# Temctrl_O.net
KiCad netlist of a schematic drawn in Altium Designer
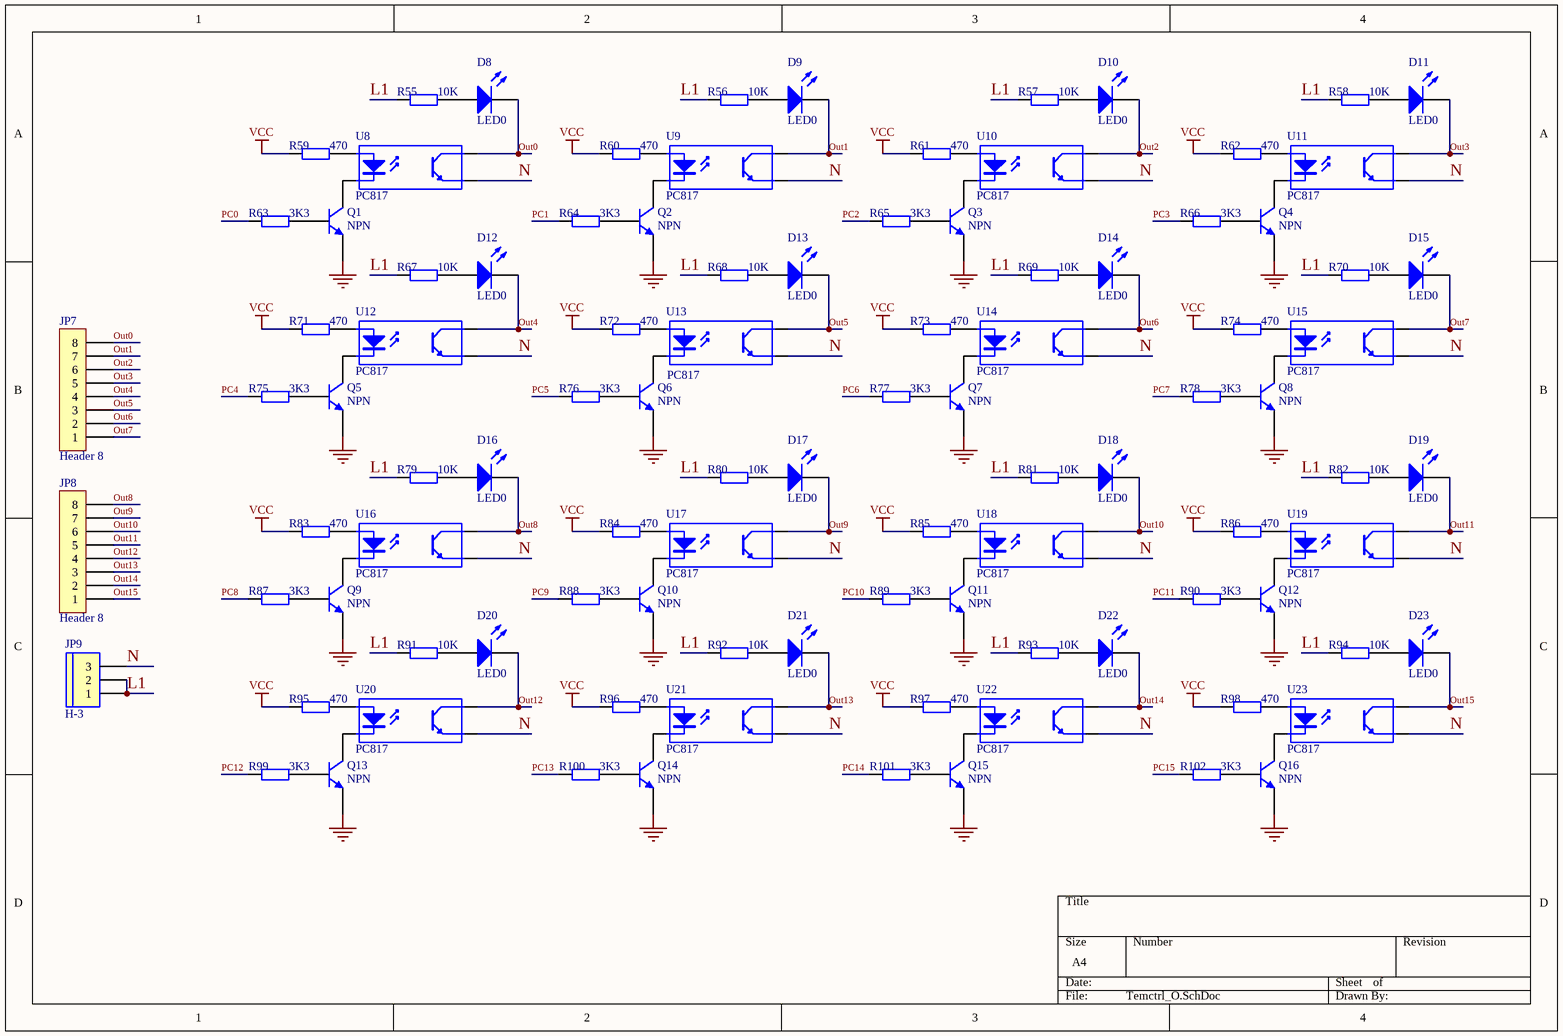
[diagram p0: Temctrl_O.SchDoc]

(export (version "E")
  (design (tool "Eeschema 10.0.6"))
  (components
    (comp (ref "D8")
      (value "LED0")
      (footprint "LED0.1-0.22")
      (description "Typical INFRARED GaAs LED")
      (fields (field (name "PUBLISHER") "Altium Limited"))
      (libsource (lib "Miscellaneous Devices") (part "LED0"))
    )
    (comp (ref "D9")
      (value "LED0")
      (footprint "LED0.1-0.22")
      (description "Typical INFRARED GaAs LED")
      (fields (field (name "PUBLISHER") "Altium Limited"))
      (libsource (lib "Miscellaneous Devices") (part "LED0"))
    )
    (comp (ref "D10")
      (value "LED0")
      (footprint "LED0.1-0.22")
      (description "Typical INFRARED GaAs LED")
      (fields (field (name "PUBLISHER") "Altium Limited"))
      (libsource (lib "Miscellaneous Devices") (part "LED0"))
    )
    (comp (ref "D11")
      (value "LED0")
      (footprint "LED0.1-0.22")
      (description "Typical INFRARED GaAs LED")
      (fields (field (name "PUBLISHER") "Altium Limited"))
      (libsource (lib "Miscellaneous Devices") (part "LED0"))
    )
    (comp (ref "D12")
      (value "LED0")
      (footprint "LED0.1-0.22")
      (description "Typical INFRARED GaAs LED")
      (fields (field (name "PUBLISHER") "Altium Limited"))
      (libsource (lib "Miscellaneous Devices") (part "LED0"))
    )
    (comp (ref "D13")
      (value "LED0")
      (footprint "LED0.1-0.22")
      (description "Typical INFRARED GaAs LED")
      (fields (field (name "PUBLISHER") "Altium Limited"))
      (libsource (lib "Miscellaneous Devices") (part "LED0"))
    )
    (comp (ref "D14")
      (value "LED0")
      (footprint "LED0.1-0.22")
      (description "Typical INFRARED GaAs LED")
      (fields (field (name "PUBLISHER") "Altium Limited"))
      (libsource (lib "Miscellaneous Devices") (part "LED0"))
    )
    (comp (ref "D15")
      (value "LED0")
      (footprint "LED0.1-0.22")
      (description "Typical INFRARED GaAs LED")
      (fields (field (name "PUBLISHER") "Altium Limited"))
      (libsource (lib "Miscellaneous Devices") (part "LED0"))
    )
    (comp (ref "D16")
      (value "LED0")
      (footprint "LED0.1-0.22")
      (description "Typical INFRARED GaAs LED")
      (fields (field (name "PUBLISHER") "Altium Limited"))
      (libsource (lib "Miscellaneous Devices") (part "LED0"))
    )
    (comp (ref "D17")
      (value "LED0")
      (footprint "LED0.1-0.22")
      (description "Typical INFRARED GaAs LED")
      (fields (field (name "PUBLISHER") "Altium Limited"))
      (libsource (lib "Miscellaneous Devices") (part "LED0"))
    )
    (comp (ref "D18")
      (value "LED0")
      (footprint "LED0.1-0.22")
      (description "Typical INFRARED GaAs LED")
      (fields (field (name "PUBLISHER") "Altium Limited"))
      (libsource (lib "Miscellaneous Devices") (part "LED0"))
    )
    (comp (ref "D19")
      (value "LED0")
      (footprint "LED0.1-0.22")
      (description "Typical INFRARED GaAs LED")
      (fields (field (name "PUBLISHER") "Altium Limited"))
      (libsource (lib "Miscellaneous Devices") (part "LED0"))
    )
    (comp (ref "D20")
      (value "LED0")
      (footprint "LED0.1-0.22")
      (description "Typical INFRARED GaAs LED")
      (fields (field (name "PUBLISHER") "Altium Limited"))
      (libsource (lib "Miscellaneous Devices") (part "LED0"))
    )
    (comp (ref "D21")
      (value "LED0")
      (footprint "LED0.1-0.22")
      (description "Typical INFRARED GaAs LED")
      (fields (field (name "PUBLISHER") "Altium Limited"))
      (libsource (lib "Miscellaneous Devices") (part "LED0"))
    )
    (comp (ref "D22")
      (value "LED0")
      (footprint "LED0.1-0.22")
      (description "Typical INFRARED GaAs LED")
      (fields (field (name "PUBLISHER") "Altium Limited"))
      (libsource (lib "Miscellaneous Devices") (part "LED0"))
    )
    (comp (ref "D23")
      (value "LED0")
      (footprint "LED0.1-0.22")
      (description "Typical INFRARED GaAs LED")
      (fields (field (name "PUBLISHER") "Altium Limited"))
      (libsource (lib "Miscellaneous Devices") (part "LED0"))
    )
    (comp (ref "JP7")
      (value "Header 8")
      (footprint "HEAD8B-H - X")
      (description "Header, 8-Pin")
      (fields (field (name "MANUFACTURER") "Generic Components"))
      (libsource (lib "HGH") (part "Header 8"))
    )
    (comp (ref "JP8")
      (value "Header 8")
      (footprint "HEAD8B-H - X")
      (description "Header, 8-Pin")
      (fields (field (name "MANUFACTURER") "Generic Components"))
      (libsource (lib "HGH") (part "Header 8"))
    )
    (comp (ref "JP9")
      (value "H-3")
      (footprint "P3")
      (description "Header, 3-Pin")
      (fields (field (name "MANUFACTURER") "Generic Components"))
      (libsource (lib "HGH") (part "H-3"))
    )
    (comp (ref "Q1")
      (value "NPN")
      (footprint "S9013SMD")
      (description "NPN Bipolar Transistor")
      (fields (field (name "PUBLISHER") "Altium Limited"))
      (libsource (lib "Miscellaneous Devices") (part "NPN"))
    )
    (comp (ref "Q2")
      (value "NPN")
      (footprint "S9013SMD")
      (description "NPN Bipolar Transistor")
      (fields (field (name "PUBLISHER") "Altium Limited"))
      (libsource (lib "Miscellaneous Devices") (part "NPN"))
    )
    (comp (ref "Q3")
      (value "NPN")
      (footprint "S9013SMD")
      (description "NPN Bipolar Transistor")
      (fields (field (name "PUBLISHER") "Altium Limited"))
      (libsource (lib "Miscellaneous Devices") (part "NPN"))
    )
    (comp (ref "Q4")
      (value "NPN")
      (footprint "S9013SMD")
      (description "NPN Bipolar Transistor")
      (fields (field (name "PUBLISHER") "Altium Limited"))
      (libsource (lib "Miscellaneous Devices") (part "NPN"))
    )
    (comp (ref "Q5")
      (value "NPN")
      (footprint "S9013SMD")
      (description "NPN Bipolar Transistor")
      (fields (field (name "PUBLISHER") "Altium Limited"))
      (libsource (lib "Miscellaneous Devices") (part "NPN"))
    )
    (comp (ref "Q6")
      (value "NPN")
      (footprint "S9013SMD")
      (description "NPN Bipolar Transistor")
      (fields (field (name "PUBLISHER") "Altium Limited"))
      (libsource (lib "Miscellaneous Devices") (part "NPN"))
    )
    (comp (ref "Q7")
      (value "NPN")
      (footprint "S9013SMD")
      (description "NPN Bipolar Transistor")
      (fields (field (name "PUBLISHER") "Altium Limited"))
      (libsource (lib "Miscellaneous Devices") (part "NPN"))
    )
    (comp (ref "Q8")
      (value "NPN")
      (footprint "S9013SMD")
      (description "NPN Bipolar Transistor")
      (fields (field (name "PUBLISHER") "Altium Limited"))
      (libsource (lib "Miscellaneous Devices") (part "NPN"))
    )
    (comp (ref "Q9")
      (value "NPN")
      (footprint "S9013SMD")
      (description "NPN Bipolar Transistor")
      (fields (field (name "PUBLISHER") "Altium Limited"))
      (libsource (lib "Miscellaneous Devices") (part "NPN"))
    )
    (comp (ref "Q10")
      (value "NPN")
      (footprint "S9013SMD")
      (description "NPN Bipolar Transistor")
      (fields (field (name "PUBLISHER") "Altium Limited"))
      (libsource (lib "Miscellaneous Devices") (part "NPN"))
    )
    (comp (ref "Q11")
      (value "NPN")
      (footprint "S9013SMD")
      (description "NPN Bipolar Transistor")
      (fields (field (name "PUBLISHER") "Altium Limited"))
      (libsource (lib "Miscellaneous Devices") (part "NPN"))
    )
    (comp (ref "Q12")
      (value "NPN")
      (footprint "S9013SMD")
      (description "NPN Bipolar Transistor")
      (fields (field (name "PUBLISHER") "Altium Limited"))
      (libsource (lib "Miscellaneous Devices") (part "NPN"))
    )
    (comp (ref "Q13")
      (value "NPN")
      (footprint "S9013SMD")
      (description "NPN Bipolar Transistor")
      (fields (field (name "PUBLISHER") "Altium Limited"))
      (libsource (lib "Miscellaneous Devices") (part "NPN"))
    )
    (comp (ref "Q14")
      (value "NPN")
      (footprint "S9013SMD")
      (description "NPN Bipolar Transistor")
      (fields (field (name "PUBLISHER") "Altium Limited"))
      (libsource (lib "Miscellaneous Devices") (part "NPN"))
    )
    (comp (ref "Q15")
      (value "NPN")
      (footprint "S9013SMD")
      (description "NPN Bipolar Transistor")
      (fields (field (name "PUBLISHER") "Altium Limited"))
      (libsource (lib "Miscellaneous Devices") (part "NPN"))
    )
    (comp (ref "Q16")
      (value "NPN")
      (footprint "S9013SMD")
      (description "NPN Bipolar Transistor")
      (fields (field (name "PUBLISHER") "Altium Limited"))
      (libsource (lib "Miscellaneous Devices") (part "NPN"))
    )
    (comp (ref "R55")
      (value "10K")
      (footprint "0805")
      (description "Resistor")
      (fields
        (field (name "MANUFACTURER") "Generic Components")
        (field (name "PUBLISHER") "Altium Hobart Technology Centre")
      )
      (libsource (lib "HGH") (part "Res"))
    )
    (comp (ref "R56")
      (value "10K")
      (footprint "0805")
      (description "Resistor")
      (fields
        (field (name "MANUFACTURER") "Generic Components")
        (field (name "PUBLISHER") "Altium Hobart Technology Centre")
      )
      (libsource (lib "HGH") (part "Res"))
    )
    (comp (ref "R57")
      (value "10K")
      (footprint "0805")
      (description "Resistor")
      (fields
        (field (name "MANUFACTURER") "Generic Components")
        (field (name "PUBLISHER") "Altium Hobart Technology Centre")
      )
      (libsource (lib "HGH") (part "Res"))
    )
    (comp (ref "R58")
      (value "10K")
      (footprint "0805")
      (description "Resistor")
      (fields
        (field (name "MANUFACTURER") "Generic Components")
        (field (name "PUBLISHER") "Altium Hobart Technology Centre")
      )
      (libsource (lib "HGH") (part "Res"))
    )
    (comp (ref "R59")
      (value "470")
      (footprint "0805")
      (description "Resistor")
      (fields
        (field (name "MANUFACTURER") "Generic Components")
        (field (name "PUBLISHER") "Altium Hobart Technology Centre")
      )
      (libsource (lib "HGH") (part "Res"))
    )
    (comp (ref "R60")
      (value "470")
      (footprint "0805")
      (description "Resistor")
      (fields
        (field (name "MANUFACTURER") "Generic Components")
        (field (name "PUBLISHER") "Altium Hobart Technology Centre")
      )
      (libsource (lib "HGH") (part "Res"))
    )
    (comp (ref "R61")
      (value "470")
      (footprint "0805")
      (description "Resistor")
      (fields
        (field (name "MANUFACTURER") "Generic Components")
        (field (name "PUBLISHER") "Altium Hobart Technology Centre")
      )
      (libsource (lib "HGH") (part "Res"))
    )
    (comp (ref "R62")
      (value "470")
      (footprint "0805")
      (description "Resistor")
      (fields
        (field (name "MANUFACTURER") "Generic Components")
        (field (name "PUBLISHER") "Altium Hobart Technology Centre")
      )
      (libsource (lib "HGH") (part "Res"))
    )
    (comp (ref "R63")
      (value "3K3")
      (footprint "0805")
      (description "Resistor")
      (fields
        (field (name "MANUFACTURER") "Generic Components")
        (field (name "PUBLISHER") "Altium Hobart Technology Centre")
      )
      (libsource (lib "HGH") (part "Res"))
    )
    (comp (ref "R64")
      (value "3K3")
      (footprint "0805")
      (description "Resistor")
      (fields
        (field (name "MANUFACTURER") "Generic Components")
        (field (name "PUBLISHER") "Altium Hobart Technology Centre")
      )
      (libsource (lib "HGH") (part "Res"))
    )
    (comp (ref "R65")
      (value "3K3")
      (footprint "0805")
      (description "Resistor")
      (fields
        (field (name "MANUFACTURER") "Generic Components")
        (field (name "PUBLISHER") "Altium Hobart Technology Centre")
      )
      (libsource (lib "HGH") (part "Res"))
    )
    (comp (ref "R66")
      (value "3K3")
      (footprint "0805")
      (description "Resistor")
      (fields
        (field (name "MANUFACTURER") "Generic Components")
        (field (name "PUBLISHER") "Altium Hobart Technology Centre")
      )
      (libsource (lib "HGH") (part "Res"))
    )
    (comp (ref "R67")
      (value "10K")
      (footprint "0805")
      (description "Resistor")
      (fields
        (field (name "MANUFACTURER") "Generic Components")
        (field (name "PUBLISHER") "Altium Hobart Technology Centre")
      )
      (libsource (lib "HGH") (part "Res"))
    )
    (comp (ref "R68")
      (value "10K")
      (footprint "0805")
      (description "Resistor")
      (fields
        (field (name "MANUFACTURER") "Generic Components")
        (field (name "PUBLISHER") "Altium Hobart Technology Centre")
      )
      (libsource (lib "HGH") (part "Res"))
    )
    (comp (ref "R69")
      (value "10K")
      (footprint "0805")
      (description "Resistor")
      (fields
        (field (name "MANUFACTURER") "Generic Components")
        (field (name "PUBLISHER") "Altium Hobart Technology Centre")
      )
      (libsource (lib "HGH") (part "Res"))
    )
    (comp (ref "R70")
      (value "10K")
      (footprint "0805")
      (description "Resistor")
      (fields
        (field (name "MANUFACTURER") "Generic Components")
        (field (name "PUBLISHER") "Altium Hobart Technology Centre")
      )
      (libsource (lib "HGH") (part "Res"))
    )
    (comp (ref "R71")
      (value "470")
      (footprint "0805")
      (description "Resistor")
      (fields
        (field (name "MANUFACTURER") "Generic Components")
        (field (name "PUBLISHER") "Altium Hobart Technology Centre")
      )
      (libsource (lib "HGH") (part "Res"))
    )
    (comp (ref "R72")
      (value "470")
      (footprint "0805")
      (description "Resistor")
      (fields
        (field (name "MANUFACTURER") "Generic Components")
        (field (name "PUBLISHER") "Altium Hobart Technology Centre")
      )
      (libsource (lib "HGH") (part "Res"))
    )
    (comp (ref "R73")
      (value "470")
      (footprint "0805")
      (description "Resistor")
      (fields
        (field (name "MANUFACTURER") "Generic Components")
        (field (name "PUBLISHER") "Altium Hobart Technology Centre")
      )
      (libsource (lib "HGH") (part "Res"))
    )
    (comp (ref "R74")
      (value "470")
      (footprint "0805")
      (description "Resistor")
      (fields
        (field (name "MANUFACTURER") "Generic Components")
        (field (name "PUBLISHER") "Altium Hobart Technology Centre")
      )
      (libsource (lib "HGH") (part "Res"))
    )
    (comp (ref "R75")
      (value "3K3")
      (footprint "0805")
      (description "Resistor")
      (fields
        (field (name "MANUFACTURER") "Generic Components")
        (field (name "PUBLISHER") "Altium Hobart Technology Centre")
      )
      (libsource (lib "HGH") (part "Res"))
    )
    (comp (ref "R76")
      (value "3K3")
      (footprint "0805")
      (description "Resistor")
      (fields
        (field (name "MANUFACTURER") "Generic Components")
        (field (name "PUBLISHER") "Altium Hobart Technology Centre")
      )
      (libsource (lib "HGH") (part "Res"))
    )
    (comp (ref "R77")
      (value "3K3")
      (footprint "0805")
      (description "Resistor")
      (fields
        (field (name "MANUFACTURER") "Generic Components")
        (field (name "PUBLISHER") "Altium Hobart Technology Centre")
      )
      (libsource (lib "HGH") (part "Res"))
    )
    (comp (ref "R78")
      (value "3K3")
      (footprint "0805")
      (description "Resistor")
      (fields
        (field (name "MANUFACTURER") "Generic Components")
        (field (name "PUBLISHER") "Altium Hobart Technology Centre")
      )
      (libsource (lib "HGH") (part "Res"))
    )
    (comp (ref "R79")
      (value "10K")
      (footprint "0805")
      (description "Resistor")
      (fields
        (field (name "MANUFACTURER") "Generic Components")
        (field (name "PUBLISHER") "Altium Hobart Technology Centre")
      )
      (libsource (lib "HGH") (part "Res"))
    )
    (comp (ref "R80")
      (value "10K")
      (footprint "0805")
      (description "Resistor")
      (fields
        (field (name "MANUFACTURER") "Generic Components")
        (field (name "PUBLISHER") "Altium Hobart Technology Centre")
      )
      (libsource (lib "HGH") (part "Res"))
    )
    (comp (ref "R81")
      (value "10K")
      (footprint "0805")
      (description "Resistor")
      (fields
        (field (name "MANUFACTURER") "Generic Components")
        (field (name "PUBLISHER") "Altium Hobart Technology Centre")
      )
      (libsource (lib "HGH") (part "Res"))
    )
    (comp (ref "R82")
      (value "10K")
      (footprint "0805")
      (description "Resistor")
      (fields
        (field (name "MANUFACTURER") "Generic Components")
        (field (name "PUBLISHER") "Altium Hobart Technology Centre")
      )
      (libsource (lib "HGH") (part "Res"))
    )
    (comp (ref "R83")
      (value "470")
      (footprint "0805")
      (description "Resistor")
      (fields
        (field (name "MANUFACTURER") "Generic Components")
        (field (name "PUBLISHER") "Altium Hobart Technology Centre")
      )
      (libsource (lib "HGH") (part "Res"))
    )
    (comp (ref "R84")
      (value "470")
      (footprint "0805")
      (description "Resistor")
      (fields
        (field (name "MANUFACTURER") "Generic Components")
        (field (name "PUBLISHER") "Altium Hobart Technology Centre")
      )
      (libsource (lib "HGH") (part "Res"))
    )
    (comp (ref "R85")
      (value "470")
      (footprint "0805")
      (description "Resistor")
      (fields
        (field (name "MANUFACTURER") "Generic Components")
        (field (name "PUBLISHER") "Altium Hobart Technology Centre")
      )
      (libsource (lib "HGH") (part "Res"))
    )
    (comp (ref "R86")
      (value "470")
      (footprint "0805")
      (description "Resistor")
      (fields
        (field (name "MANUFACTURER") "Generic Components")
        (field (name "PUBLISHER") "Altium Hobart Technology Centre")
      )
      (libsource (lib "HGH") (part "Res"))
    )
    (comp (ref "R87")
      (value "3K3")
      (footprint "0805")
      (description "Resistor")
      (fields
        (field (name "MANUFACTURER") "Generic Components")
        (field (name "PUBLISHER") "Altium Hobart Technology Centre")
      )
      (libsource (lib "HGH") (part "Res"))
    )
    (comp (ref "R88")
      (value "3K3")
      (footprint "0805")
      (description "Resistor")
      (fields
        (field (name "MANUFACTURER") "Generic Components")
        (field (name "PUBLISHER") "Altium Hobart Technology Centre")
      )
      (libsource (lib "HGH") (part "Res"))
    )
    (comp (ref "R89")
      (value "3K3")
      (footprint "0805")
      (description "Resistor")
      (fields
        (field (name "MANUFACTURER") "Generic Components")
        (field (name "PUBLISHER") "Altium Hobart Technology Centre")
      )
      (libsource (lib "HGH") (part "Res"))
    )
    (comp (ref "R90")
      (value "3K3")
      (footprint "0805")
      (description "Resistor")
      (fields
        (field (name "MANUFACTURER") "Generic Components")
        (field (name "PUBLISHER") "Altium Hobart Technology Centre")
      )
      (libsource (lib "HGH") (part "Res"))
    )
    (comp (ref "R91")
      (value "10K")
      (footprint "0805")
      (description "Resistor")
      (fields
        (field (name "MANUFACTURER") "Generic Components")
        (field (name "PUBLISHER") "Altium Hobart Technology Centre")
      )
      (libsource (lib "HGH") (part "Res"))
    )
    (comp (ref "R92")
      (value "10K")
      (footprint "0805")
      (description "Resistor")
      (fields
        (field (name "MANUFACTURER") "Generic Components")
        (field (name "PUBLISHER") "Altium Hobart Technology Centre")
      )
      (libsource (lib "HGH") (part "Res"))
    )
    (comp (ref "R93")
      (value "10K")
      (footprint "0805")
      (description "Resistor")
      (fields
        (field (name "MANUFACTURER") "Generic Components")
        (field (name "PUBLISHER") "Altium Hobart Technology Centre")
      )
      (libsource (lib "HGH") (part "Res"))
    )
    (comp (ref "R94")
      (value "10K")
      (footprint "0805")
      (description "Resistor")
      (fields
        (field (name "MANUFACTURER") "Generic Components")
        (field (name "PUBLISHER") "Altium Hobart Technology Centre")
      )
      (libsource (lib "HGH") (part "Res"))
    )
    (comp (ref "R95")
      (value "470")
      (footprint "0805")
      (description "Resistor")
      (fields
        (field (name "MANUFACTURER") "Generic Components")
        (field (name "PUBLISHER") "Altium Hobart Technology Centre")
      )
      (libsource (lib "HGH") (part "Res"))
    )
    (comp (ref "R96")
      (value "470")
      (footprint "0805")
      (description "Resistor")
      (fields
        (field (name "MANUFACTURER") "Generic Components")
        (field (name "PUBLISHER") "Altium Hobart Technology Centre")
      )
      (libsource (lib "HGH") (part "Res"))
    )
    (comp (ref "R97")
      (value "470")
      (footprint "0805")
      (description "Resistor")
      (fields
        (field (name "MANUFACTURER") "Generic Components")
        (field (name "PUBLISHER") "Altium Hobart Technology Centre")
      )
      (libsource (lib "HGH") (part "Res"))
    )
    (comp (ref "R98")
      (value "470")
      (footprint "0805")
      (description "Resistor")
      (fields
        (field (name "MANUFACTURER") "Generic Components")
        (field (name "PUBLISHER") "Altium Hobart Technology Centre")
      )
      (libsource (lib "HGH") (part "Res"))
    )
    (comp (ref "R99")
      (value "3K3")
      (footprint "0805")
      (description "Resistor")
      (fields
        (field (name "MANUFACTURER") "Generic Components")
        (field (name "PUBLISHER") "Altium Hobart Technology Centre")
      )
      (libsource (lib "HGH") (part "Res"))
    )
    (comp (ref "R100")
      (value "3K3")
      (footprint "0805")
      (description "Resistor")
      (fields
        (field (name "MANUFACTURER") "Generic Components")
        (field (name "PUBLISHER") "Altium Hobart Technology Centre")
      )
      (libsource (lib "HGH") (part "Res"))
    )
    (comp (ref "R101")
      (value "3K3")
      (footprint "0805")
      (description "Resistor")
      (fields
        (field (name "MANUFACTURER") "Generic Components")
        (field (name "PUBLISHER") "Altium Hobart Technology Centre")
      )
      (libsource (lib "HGH") (part "Res"))
    )
    (comp (ref "R102")
      (value "3K3")
      (footprint "0805")
      (description "Resistor")
      (fields
        (field (name "MANUFACTURER") "Generic Components")
        (field (name "PUBLISHER") "Altium Hobart Technology Centre")
      )
      (libsource (lib "HGH") (part "Res"))
    )
    (comp (ref "U8")
      (value "PC817")
      (footprint "DIP-4")
      (description "4-Pin Phototransistor Optocoupler")
      (fields (field (name "PUBLISHER") "Altium Limited"))
      (libsource (lib "Miscellaneous Devices") (part "Optoisolator1"))
    )
    (comp (ref "U9")
      (value "PC817")
      (footprint "DIP-4")
      (description "4-Pin Phototransistor Optocoupler")
      (fields (field (name "PUBLISHER") "Altium Limited"))
      (libsource (lib "Miscellaneous Devices") (part "Optoisolator1"))
    )
    (comp (ref "U10")
      (value "PC817")
      (footprint "DIP-4")
      (description "4-Pin Phototransistor Optocoupler")
      (fields (field (name "PUBLISHER") "Altium Limited"))
      (libsource (lib "Miscellaneous Devices") (part "Optoisolator1"))
    )
    (comp (ref "U11")
      (value "PC817")
      (footprint "DIP-4")
      (description "4-Pin Phototransistor Optocoupler")
      (fields (field (name "PUBLISHER") "Altium Limited"))
      (libsource (lib "Miscellaneous Devices") (part "Optoisolator1"))
    )
    (comp (ref "U12")
      (value "PC817")
      (footprint "DIP-4")
      (description "4-Pin Phototransistor Optocoupler")
      (fields (field (name "PUBLISHER") "Altium Limited"))
      (libsource (lib "Miscellaneous Devices") (part "Optoisolator1"))
    )
    (comp (ref "U13")
      (value "PC817")
      (footprint "DIP-4")
      (description "4-Pin Phototransistor Optocoupler")
      (fields (field (name "PUBLISHER") "Altium Limited"))
      (libsource (lib "Miscellaneous Devices") (part "Optoisolator1"))
    )
    (comp (ref "U14")
      (value "PC817")
      (footprint "DIP-4")
      (description "4-Pin Phototransistor Optocoupler")
      (fields (field (name "PUBLISHER") "Altium Limited"))
      (libsource (lib "Miscellaneous Devices") (part "Optoisolator1"))
    )
    (comp (ref "U15")
      (value "PC817")
      (footprint "DIP-4")
      (description "4-Pin Phototransistor Optocoupler")
      (fields (field (name "PUBLISHER") "Altium Limited"))
      (libsource (lib "Miscellaneous Devices") (part "Optoisolator1"))
    )
    (comp (ref "U16")
      (value "PC817")
      (footprint "DIP-4")
      (description "4-Pin Phototransistor Optocoupler")
      (fields (field (name "PUBLISHER") "Altium Limited"))
      (libsource (lib "Miscellaneous Devices") (part "Optoisolator1"))
    )
    (comp (ref "U17")
      (value "PC817")
      (footprint "DIP-4")
      (description "4-Pin Phototransistor Optocoupler")
      (fields (field (name "PUBLISHER") "Altium Limited"))
      (libsource (lib "Miscellaneous Devices") (part "Optoisolator1"))
    )
    (comp (ref "U18")
      (value "PC817")
      (footprint "DIP-4")
      (description "4-Pin Phototransistor Optocoupler")
      (fields (field (name "PUBLISHER") "Altium Limited"))
      (libsource (lib "Miscellaneous Devices") (part "Optoisolator1"))
    )
    (comp (ref "U19")
      (value "PC817")
      (footprint "DIP-4")
      (description "4-Pin Phototransistor Optocoupler")
      (fields (field (name "PUBLISHER") "Altium Limited"))
      (libsource (lib "Miscellaneous Devices") (part "Optoisolator1"))
    )
    (comp (ref "U20")
      (value "PC817")
      (footprint "DIP-4")
      (description "4-Pin Phototransistor Optocoupler")
      (fields (field (name "PUBLISHER") "Altium Limited"))
      (libsource (lib "Miscellaneous Devices") (part "Optoisolator1"))
    )
    (comp (ref "U21")
      (value "PC817")
      (footprint "DIP-4")
      (description "4-Pin Phototransistor Optocoupler")
      (fields (field (name "PUBLISHER") "Altium Limited"))
      (libsource (lib "Miscellaneous Devices") (part "Optoisolator1"))
    )
    (comp (ref "U22")
      (value "PC817")
      (footprint "DIP-4")
      (description "4-Pin Phototransistor Optocoupler")
      (fields (field (name "PUBLISHER") "Altium Limited"))
      (libsource (lib "Miscellaneous Devices") (part "Optoisolator1"))
    )
    (comp (ref "U23")
      (value "PC817")
      (footprint "DIP-4")
      (description "4-Pin Phototransistor Optocoupler")
      (fields (field (name "PUBLISHER") "Altium Limited"))
      (libsource (lib "Miscellaneous Devices") (part "Optoisolator1"))
    )
  )
  (nets
    (net (code "1") (name "/L1") (class "Default")
      (node (ref "JP9") (pin "1") (pinfunction "1_1") (pintype "passive"))
      (node (ref "JP9") (pin "2") (pinfunction "2_2") (pintype "passive"))
      (node (ref "R55") (pin "1") (pinfunction "1_1") (pintype "passive"))
      (node (ref "R56") (pin "1") (pinfunction "1_1") (pintype "passive"))
      (node (ref "R57") (pin "1") (pinfunction "1_1") (pintype "passive"))
      (node (ref "R58") (pin "1") (pinfunction "1_1") (pintype "passive"))
      (node (ref "R67") (pin "1") (pinfunction "1_1") (pintype "passive"))
      (node (ref "R68") (pin "1") (pinfunction "1_1") (pintype "passive"))
      (node (ref "R69") (pin "1") (pinfunction "1_1") (pintype "passive"))
      (node (ref "R70") (pin "1") (pinfunction "1_1") (pintype "passive"))
      (node (ref "R79") (pin "1") (pinfunction "1_1") (pintype "passive"))
      (node (ref "R80") (pin "1") (pinfunction "1_1") (pintype "passive"))
      (node (ref "R81") (pin "1") (pinfunction "1_1") (pintype "passive"))
      (node (ref "R82") (pin "1") (pinfunction "1_1") (pintype "passive"))
      (node (ref "R91") (pin "1") (pinfunction "1_1") (pintype "passive"))
      (node (ref "R92") (pin "1") (pinfunction "1_1") (pintype "passive"))
      (node (ref "R93") (pin "1") (pinfunction "1_1") (pintype "passive"))
      (node (ref "R94") (pin "1") (pinfunction "1_1") (pintype "passive"))
    )
    (net (code "2") (name "/N") (class "Default")
      (node (ref "JP9") (pin "3") (pinfunction "3_3") (pintype "passive"))
      (node (ref "U10") (pin "3") (pinfunction "E_3") (pintype "passive"))
      (node (ref "U11") (pin "3") (pinfunction "E_3") (pintype "passive"))
      (node (ref "U12") (pin "3") (pinfunction "E_3") (pintype "passive"))
      (node (ref "U13") (pin "3") (pinfunction "E_3") (pintype "passive"))
      (node (ref "U14") (pin "3") (pinfunction "E_3") (pintype "passive"))
      (node (ref "U15") (pin "3") (pinfunction "E_3") (pintype "passive"))
      (node (ref "U16") (pin "3") (pinfunction "E_3") (pintype "passive"))
      (node (ref "U17") (pin "3") (pinfunction "E_3") (pintype "passive"))
      (node (ref "U18") (pin "3") (pinfunction "E_3") (pintype "passive"))
      (node (ref "U19") (pin "3") (pinfunction "E_3") (pintype "passive"))
      (node (ref "U20") (pin "3") (pinfunction "E_3") (pintype "passive"))
      (node (ref "U21") (pin "3") (pinfunction "E_3") (pintype "passive"))
      (node (ref "U22") (pin "3") (pinfunction "E_3") (pintype "passive"))
      (node (ref "U23") (pin "3") (pinfunction "E_3") (pintype "passive"))
      (node (ref "U8") (pin "3") (pinfunction "E_3") (pintype "passive"))
      (node (ref "U9") (pin "3") (pinfunction "E_3") (pintype "passive"))
    )
    (net (code "3") (name "/Out0") (class "Default")
      (node (ref "D8") (pin "2") (pinfunction "K_2") (pintype "passive"))
      (node (ref "JP7") (pin "8") (pinfunction "8_8") (pintype "passive"))
      (node (ref "U8") (pin "4") (pinfunction "C_4") (pintype "passive"))
    )
    (net (code "4") (name "/Out1") (class "Default")
      (node (ref "D9") (pin "2") (pinfunction "K_2") (pintype "passive"))
      (node (ref "JP7") (pin "7") (pinfunction "7_7") (pintype "passive"))
      (node (ref "U9") (pin "4") (pinfunction "C_4") (pintype "passive"))
    )
    (net (code "5") (name "/Out2") (class "Default")
      (node (ref "D10") (pin "2") (pinfunction "K_2") (pintype "passive"))
      (node (ref "JP7") (pin "6") (pinfunction "6_6") (pintype "passive"))
      (node (ref "U10") (pin "4") (pinfunction "C_4") (pintype "passive"))
    )
    (net (code "6") (name "/Out3") (class "Default")
      (node (ref "D11") (pin "2") (pinfunction "K_2") (pintype "passive"))
      (node (ref "JP7") (pin "5") (pinfunction "5_5") (pintype "passive"))
      (node (ref "U11") (pin "4") (pinfunction "C_4") (pintype "passive"))
    )
    (net (code "7") (name "/Out4") (class "Default")
      (node (ref "D12") (pin "2") (pinfunction "K_2") (pintype "passive"))
      (node (ref "JP7") (pin "4") (pinfunction "4_4") (pintype "passive"))
      (node (ref "U12") (pin "4") (pinfunction "C_4") (pintype "passive"))
    )
    (net (code "8") (name "/Out5") (class "Default")
      (node (ref "D13") (pin "2") (pinfunction "K_2") (pintype "passive"))
      (node (ref "JP7") (pin "3") (pinfunction "3_3") (pintype "passive"))
      (node (ref "U13") (pin "4") (pinfunction "C_4") (pintype "passive"))
    )
    (net (code "9") (name "/Out6") (class "Default")
      (node (ref "D14") (pin "2") (pinfunction "K_2") (pintype "passive"))
      (node (ref "JP7") (pin "2") (pinfunction "2_2") (pintype "passive"))
      (node (ref "U14") (pin "4") (pinfunction "C_4") (pintype "passive"))
    )
    (net (code "10") (name "/Out7") (class "Default")
      (node (ref "D15") (pin "2") (pinfunction "K_2") (pintype "passive"))
      (node (ref "JP7") (pin "1") (pinfunction "1_1") (pintype "passive"))
      (node (ref "U15") (pin "4") (pinfunction "C_4") (pintype "passive"))
    )
    (net (code "11") (name "/Out8") (class "Default")
      (node (ref "D16") (pin "2") (pinfunction "K_2") (pintype "passive"))
      (node (ref "JP8") (pin "8") (pinfunction "8_8") (pintype "passive"))
      (node (ref "U16") (pin "4") (pinfunction "C_4") (pintype "passive"))
    )
    (net (code "12") (name "/Out9") (class "Default")
      (node (ref "D17") (pin "2") (pinfunction "K_2") (pintype "passive"))
      (node (ref "JP8") (pin "7") (pinfunction "7_7") (pintype "passive"))
      (node (ref "U17") (pin "4") (pinfunction "C_4") (pintype "passive"))
    )
    (net (code "13") (name "/Out10") (class "Default")
      (node (ref "D18") (pin "2") (pinfunction "K_2") (pintype "passive"))
      (node (ref "JP8") (pin "6") (pinfunction "6_6") (pintype "passive"))
      (node (ref "U18") (pin "4") (pinfunction "C_4") (pintype "passive"))
    )
    (net (code "14") (name "/Out11") (class "Default")
      (node (ref "D19") (pin "2") (pinfunction "K_2") (pintype "passive"))
      (node (ref "JP8") (pin "5") (pinfunction "5_5") (pintype "passive"))
      (node (ref "U19") (pin "4") (pinfunction "C_4") (pintype "passive"))
    )
    (net (code "15") (name "/Out12") (class "Default")
      (node (ref "D20") (pin "2") (pinfunction "K_2") (pintype "passive"))
      (node (ref "JP8") (pin "4") (pinfunction "4_4") (pintype "passive"))
      (node (ref "U20") (pin "4") (pinfunction "C_4") (pintype "passive"))
    )
    (net (code "16") (name "/Out13") (class "Default")
      (node (ref "D21") (pin "2") (pinfunction "K_2") (pintype "passive"))
      (node (ref "JP8") (pin "3") (pinfunction "3_3") (pintype "passive"))
      (node (ref "U21") (pin "4") (pinfunction "C_4") (pintype "passive"))
    )
    (net (code "17") (name "/Out14") (class "Default")
      (node (ref "D22") (pin "2") (pinfunction "K_2") (pintype "passive"))
      (node (ref "JP8") (pin "2") (pinfunction "2_2") (pintype "passive"))
      (node (ref "U22") (pin "4") (pinfunction "C_4") (pintype "passive"))
    )
    (net (code "18") (name "/Out15") (class "Default")
      (node (ref "D23") (pin "2") (pinfunction "K_2") (pintype "passive"))
      (node (ref "JP8") (pin "1") (pinfunction "1_1") (pintype "passive"))
      (node (ref "U23") (pin "4") (pinfunction "C_4") (pintype "passive"))
    )
    (net (code "19") (name "/PC0") (class "Default")
      (node (ref "R63") (pin "1") (pinfunction "1_1") (pintype "passive"))
    )
    (net (code "20") (name "/PC1") (class "Default")
      (node (ref "R64") (pin "1") (pinfunction "1_1") (pintype "passive"))
    )
    (net (code "21") (name "/PC2") (class "Default")
      (node (ref "R65") (pin "1") (pinfunction "1_1") (pintype "passive"))
    )
    (net (code "22") (name "/PC3") (class "Default")
      (node (ref "R66") (pin "1") (pinfunction "1_1") (pintype "passive"))
    )
    (net (code "23") (name "/PC4") (class "Default")
      (node (ref "R75") (pin "1") (pinfunction "1_1") (pintype "passive"))
    )
    (net (code "24") (name "/PC5") (class "Default")
      (node (ref "R76") (pin "1") (pinfunction "1_1") (pintype "passive"))
    )
    (net (code "25") (name "/PC6") (class "Default")
      (node (ref "R77") (pin "1") (pinfunction "1_1") (pintype "passive"))
    )
    (net (code "26") (name "/PC7") (class "Default")
      (node (ref "R78") (pin "1") (pinfunction "1_1") (pintype "passive"))
    )
    (net (code "27") (name "/PC8") (class "Default")
      (node (ref "R87") (pin "1") (pinfunction "1_1") (pintype "passive"))
    )
    (net (code "28") (name "/PC9") (class "Default")
      (node (ref "R88") (pin "1") (pinfunction "1_1") (pintype "passive"))
    )
    (net (code "29") (name "/PC10") (class "Default")
      (node (ref "R89") (pin "1") (pinfunction "1_1") (pintype "passive"))
    )
    (net (code "30") (name "/PC11") (class "Default")
      (node (ref "R90") (pin "1") (pinfunction "1_1") (pintype "passive"))
    )
    (net (code "31") (name "/PC12") (class "Default")
      (node (ref "R99") (pin "1") (pinfunction "1_1") (pintype "passive"))
    )
    (net (code "32") (name "/PC13") (class "Default")
      (node (ref "R100") (pin "1") (pinfunction "1_1") (pintype "passive"))
    )
    (net (code "33") (name "/PC14") (class "Default")
      (node (ref "R101") (pin "1") (pinfunction "1_1") (pintype "passive"))
    )
    (net (code "34") (name "/PC15") (class "Default")
      (node (ref "R102") (pin "1") (pinfunction "1_1") (pintype "passive"))
    )
    (net (code "35") (name "GND") (class "Default")
      (node (ref "Q1") (pin "3") (pinfunction "E_3") (pintype "passive"))
      (node (ref "Q10") (pin "3") (pinfunction "E_3") (pintype "passive"))
      (node (ref "Q11") (pin "3") (pinfunction "E_3") (pintype "passive"))
      (node (ref "Q12") (pin "3") (pinfunction "E_3") (pintype "passive"))
      (node (ref "Q13") (pin "3") (pinfunction "E_3") (pintype "passive"))
      (node (ref "Q14") (pin "3") (pinfunction "E_3") (pintype "passive"))
      (node (ref "Q15") (pin "3") (pinfunction "E_3") (pintype "passive"))
      (node (ref "Q16") (pin "3") (pinfunction "E_3") (pintype "passive"))
      (node (ref "Q2") (pin "3") (pinfunction "E_3") (pintype "passive"))
      (node (ref "Q3") (pin "3") (pinfunction "E_3") (pintype "passive"))
      (node (ref "Q4") (pin "3") (pinfunction "E_3") (pintype "passive"))
      (node (ref "Q5") (pin "3") (pinfunction "E_3") (pintype "passive"))
      (node (ref "Q6") (pin "3") (pinfunction "E_3") (pintype "passive"))
      (node (ref "Q7") (pin "3") (pinfunction "E_3") (pintype "passive"))
      (node (ref "Q8") (pin "3") (pinfunction "E_3") (pintype "passive"))
      (node (ref "Q9") (pin "3") (pinfunction "E_3") (pintype "passive"))
    )
    (net (code "36") (name "Net-(D8-A)") (class "Default")
      (node (ref "D8") (pin "1") (pinfunction "A_1") (pintype "passive"))
      (node (ref "R55") (pin "2") (pinfunction "2_2") (pintype "passive"))
    )
    (net (code "37") (name "Net-(D9-A)") (class "Default")
      (node (ref "D9") (pin "1") (pinfunction "A_1") (pintype "passive"))
      (node (ref "R56") (pin "2") (pinfunction "2_2") (pintype "passive"))
    )
    (net (code "38") (name "Net-(D10-A)") (class "Default")
      (node (ref "D10") (pin "1") (pinfunction "A_1") (pintype "passive"))
      (node (ref "R57") (pin "2") (pinfunction "2_2") (pintype "passive"))
    )
    (net (code "39") (name "Net-(D11-A)") (class "Default")
      (node (ref "D11") (pin "1") (pinfunction "A_1") (pintype "passive"))
      (node (ref "R58") (pin "2") (pinfunction "2_2") (pintype "passive"))
    )
    (net (code "40") (name "Net-(D12-A)") (class "Default")
      (node (ref "D12") (pin "1") (pinfunction "A_1") (pintype "passive"))
      (node (ref "R67") (pin "2") (pinfunction "2_2") (pintype "passive"))
    )
    (net (code "41") (name "Net-(D13-A)") (class "Default")
      (node (ref "D13") (pin "1") (pinfunction "A_1") (pintype "passive"))
      (node (ref "R68") (pin "2") (pinfunction "2_2") (pintype "passive"))
    )
    (net (code "42") (name "Net-(D14-A)") (class "Default")
      (node (ref "D14") (pin "1") (pinfunction "A_1") (pintype "passive"))
      (node (ref "R69") (pin "2") (pinfunction "2_2") (pintype "passive"))
    )
    (net (code "43") (name "Net-(D15-A)") (class "Default")
      (node (ref "D15") (pin "1") (pinfunction "A_1") (pintype "passive"))
      (node (ref "R70") (pin "2") (pinfunction "2_2") (pintype "passive"))
    )
    (net (code "44") (name "Net-(D16-A)") (class "Default")
      (node (ref "D16") (pin "1") (pinfunction "A_1") (pintype "passive"))
      (node (ref "R79") (pin "2") (pinfunction "2_2") (pintype "passive"))
    )
    (net (code "45") (name "Net-(D17-A)") (class "Default")
      (node (ref "D17") (pin "1") (pinfunction "A_1") (pintype "passive"))
      (node (ref "R80") (pin "2") (pinfunction "2_2") (pintype "passive"))
    )
    (net (code "46") (name "Net-(D18-A)") (class "Default")
      (node (ref "D18") (pin "1") (pinfunction "A_1") (pintype "passive"))
      (node (ref "R81") (pin "2") (pinfunction "2_2") (pintype "passive"))
    )
    (net (code "47") (name "Net-(D19-A)") (class "Default")
      (node (ref "D19") (pin "1") (pinfunction "A_1") (pintype "passive"))
      (node (ref "R82") (pin "2") (pinfunction "2_2") (pintype "passive"))
    )
    (net (code "48") (name "Net-(D20-A)") (class "Default")
      (node (ref "D20") (pin "1") (pinfunction "A_1") (pintype "passive"))
      (node (ref "R91") (pin "2") (pinfunction "2_2") (pintype "passive"))
    )
    (net (code "49") (name "Net-(D21-A)") (class "Default")
      (node (ref "D21") (pin "1") (pinfunction "A_1") (pintype "passive"))
      (node (ref "R92") (pin "2") (pinfunction "2_2") (pintype "passive"))
    )
    (net (code "50") (name "Net-(D22-A)") (class "Default")
      (node (ref "D22") (pin "1") (pinfunction "A_1") (pintype "passive"))
      (node (ref "R93") (pin "2") (pinfunction "2_2") (pintype "passive"))
    )
    (net (code "51") (name "Net-(D23-A)") (class "Default")
      (node (ref "D23") (pin "1") (pinfunction "A_1") (pintype "passive"))
      (node (ref "R94") (pin "2") (pinfunction "2_2") (pintype "passive"))
    )
    (net (code "52") (name "Net-(Q1-B)") (class "Default")
      (node (ref "Q1") (pin "2") (pinfunction "B_2") (pintype "passive"))
      (node (ref "R63") (pin "2") (pinfunction "2_2") (pintype "passive"))
    )
    (net (code "53") (name "Net-(Q1-C)") (class "Default")
      (node (ref "Q1") (pin "1") (pinfunction "C_1") (pintype "passive"))
      (node (ref "U8") (pin "2") (pinfunction "K_2") (pintype "passive"))
    )
    (net (code "54") (name "Net-(Q2-B)") (class "Default")
      (node (ref "Q2") (pin "2") (pinfunction "B_2") (pintype "passive"))
      (node (ref "R64") (pin "2") (pinfunction "2_2") (pintype "passive"))
    )
    (net (code "55") (name "Net-(Q2-C)") (class "Default")
      (node (ref "Q2") (pin "1") (pinfunction "C_1") (pintype "passive"))
      (node (ref "U9") (pin "2") (pinfunction "K_2") (pintype "passive"))
    )
    (net (code "56") (name "Net-(Q3-B)") (class "Default")
      (node (ref "Q3") (pin "2") (pinfunction "B_2") (pintype "passive"))
      (node (ref "R65") (pin "2") (pinfunction "2_2") (pintype "passive"))
    )
    (net (code "57") (name "Net-(Q3-C)") (class "Default")
      (node (ref "Q3") (pin "1") (pinfunction "C_1") (pintype "passive"))
      (node (ref "U10") (pin "2") (pinfunction "K_2") (pintype "passive"))
    )
    (net (code "58") (name "Net-(Q4-B)") (class "Default")
      (node (ref "Q4") (pin "2") (pinfunction "B_2") (pintype "passive"))
      (node (ref "R66") (pin "2") (pinfunction "2_2") (pintype "passive"))
    )
    (net (code "59") (name "Net-(Q4-C)") (class "Default")
      (node (ref "Q4") (pin "1") (pinfunction "C_1") (pintype "passive"))
      (node (ref "U11") (pin "2") (pinfunction "K_2") (pintype "passive"))
    )
    (net (code "60") (name "Net-(Q5-B)") (class "Default")
      (node (ref "Q5") (pin "2") (pinfunction "B_2") (pintype "passive"))
      (node (ref "R75") (pin "2") (pinfunction "2_2") (pintype "passive"))
    )
    (net (code "61") (name "Net-(Q5-C)") (class "Default")
      (node (ref "Q5") (pin "1") (pinfunction "C_1") (pintype "passive"))
      (node (ref "U12") (pin "2") (pinfunction "K_2") (pintype "passive"))
    )
    (net (code "62") (name "Net-(Q6-B)") (class "Default")
      (node (ref "Q6") (pin "2") (pinfunction "B_2") (pintype "passive"))
      (node (ref "R76") (pin "2") (pinfunction "2_2") (pintype "passive"))
    )
    (net (code "63") (name "Net-(Q6-C)") (class "Default")
      (node (ref "Q6") (pin "1") (pinfunction "C_1") (pintype "passive"))
      (node (ref "U13") (pin "2") (pinfunction "K_2") (pintype "passive"))
    )
    (net (code "64") (name "Net-(Q7-B)") (class "Default")
      (node (ref "Q7") (pin "2") (pinfunction "B_2") (pintype "passive"))
      (node (ref "R77") (pin "2") (pinfunction "2_2") (pintype "passive"))
    )
    (net (code "65") (name "Net-(Q7-C)") (class "Default")
      (node (ref "Q7") (pin "1") (pinfunction "C_1") (pintype "passive"))
      (node (ref "U14") (pin "2") (pinfunction "K_2") (pintype "passive"))
    )
    (net (code "66") (name "Net-(Q8-B)") (class "Default")
      (node (ref "Q8") (pin "2") (pinfunction "B_2") (pintype "passive"))
      (node (ref "R78") (pin "2") (pinfunction "2_2") (pintype "passive"))
    )
    (net (code "67") (name "Net-(Q8-C)") (class "Default")
      (node (ref "Q8") (pin "1") (pinfunction "C_1") (pintype "passive"))
      (node (ref "U15") (pin "2") (pinfunction "K_2") (pintype "passive"))
    )
    (net (code "68") (name "Net-(Q9-B)") (class "Default")
      (node (ref "Q9") (pin "2") (pinfunction "B_2") (pintype "passive"))
      (node (ref "R87") (pin "2") (pinfunction "2_2") (pintype "passive"))
    )
    (net (code "69") (name "Net-(Q9-C)") (class "Default")
      (node (ref "Q9") (pin "1") (pinfunction "C_1") (pintype "passive"))
      (node (ref "U16") (pin "2") (pinfunction "K_2") (pintype "passive"))
    )
    (net (code "70") (name "Net-(Q10-B)") (class "Default")
      (node (ref "Q10") (pin "2") (pinfunction "B_2") (pintype "passive"))
      (node (ref "R88") (pin "2") (pinfunction "2_2") (pintype "passive"))
    )
    (net (code "71") (name "Net-(Q10-C)") (class "Default")
      (node (ref "Q10") (pin "1") (pinfunction "C_1") (pintype "passive"))
      (node (ref "U17") (pin "2") (pinfunction "K_2") (pintype "passive"))
    )
    (net (code "72") (name "Net-(Q11-B)") (class "Default")
      (node (ref "Q11") (pin "2") (pinfunction "B_2") (pintype "passive"))
      (node (ref "R89") (pin "2") (pinfunction "2_2") (pintype "passive"))
    )
    (net (code "73") (name "Net-(Q11-C)") (class "Default")
      (node (ref "Q11") (pin "1") (pinfunction "C_1") (pintype "passive"))
      (node (ref "U18") (pin "2") (pinfunction "K_2") (pintype "passive"))
    )
    (net (code "74") (name "Net-(Q12-B)") (class "Default")
      (node (ref "Q12") (pin "2") (pinfunction "B_2") (pintype "passive"))
      (node (ref "R90") (pin "2") (pinfunction "2_2") (pintype "passive"))
    )
    (net (code "75") (name "Net-(Q12-C)") (class "Default")
      (node (ref "Q12") (pin "1") (pinfunction "C_1") (pintype "passive"))
      (node (ref "U19") (pin "2") (pinfunction "K_2") (pintype "passive"))
    )
    (net (code "76") (name "Net-(Q13-B)") (class "Default")
      (node (ref "Q13") (pin "2") (pinfunction "B_2") (pintype "passive"))
      (node (ref "R99") (pin "2") (pinfunction "2_2") (pintype "passive"))
    )
    (net (code "77") (name "Net-(Q13-C)") (class "Default")
      (node (ref "Q13") (pin "1") (pinfunction "C_1") (pintype "passive"))
      (node (ref "U20") (pin "2") (pinfunction "K_2") (pintype "passive"))
    )
    (net (code "78") (name "Net-(Q14-B)") (class "Default")
      (node (ref "Q14") (pin "2") (pinfunction "B_2") (pintype "passive"))
      (node (ref "R100") (pin "2") (pinfunction "2_2") (pintype "passive"))
    )
    (net (code "79") (name "Net-(Q14-C)") (class "Default")
      (node (ref "Q14") (pin "1") (pinfunction "C_1") (pintype "passive"))
      (node (ref "U21") (pin "2") (pinfunction "K_2") (pintype "passive"))
    )
    (net (code "80") (name "Net-(Q15-B)") (class "Default")
      (node (ref "Q15") (pin "2") (pinfunction "B_2") (pintype "passive"))
      (node (ref "R101") (pin "2") (pinfunction "2_2") (pintype "passive"))
    )
    (net (code "81") (name "Net-(Q15-C)") (class "Default")
      (node (ref "Q15") (pin "1") (pinfunction "C_1") (pintype "passive"))
      (node (ref "U22") (pin "2") (pinfunction "K_2") (pintype "passive"))
    )
    (net (code "82") (name "Net-(Q16-B)") (class "Default")
      (node (ref "Q16") (pin "2") (pinfunction "B_2") (pintype "passive"))
      (node (ref "R102") (pin "2") (pinfunction "2_2") (pintype "passive"))
    )
    (net (code "83") (name "Net-(Q16-C)") (class "Default")
      (node (ref "Q16") (pin "1") (pinfunction "C_1") (pintype "passive"))
      (node (ref "U23") (pin "2") (pinfunction "K_2") (pintype "passive"))
    )
    (net (code "84") (name "Net-(U8-A)") (class "Default")
      (node (ref "R59") (pin "2") (pinfunction "2_2") (pintype "passive"))
      (node (ref "U8") (pin "1") (pinfunction "A_1") (pintype "passive"))
    )
    (net (code "85") (name "Net-(U9-A)") (class "Default")
      (node (ref "R60") (pin "2") (pinfunction "2_2") (pintype "passive"))
      (node (ref "U9") (pin "1") (pinfunction "A_1") (pintype "passive"))
    )
    (net (code "86") (name "Net-(U10-A)") (class "Default")
      (node (ref "R61") (pin "2") (pinfunction "2_2") (pintype "passive"))
      (node (ref "U10") (pin "1") (pinfunction "A_1") (pintype "passive"))
    )
    (net (code "87") (name "Net-(U11-A)") (class "Default")
      (node (ref "R62") (pin "2") (pinfunction "2_2") (pintype "passive"))
      (node (ref "U11") (pin "1") (pinfunction "A_1") (pintype "passive"))
    )
    (net (code "88") (name "Net-(U12-A)") (class "Default")
      (node (ref "R71") (pin "2") (pinfunction "2_2") (pintype "passive"))
      (node (ref "U12") (pin "1") (pinfunction "A_1") (pintype "passive"))
    )
    (net (code "89") (name "Net-(U13-A)") (class "Default")
      (node (ref "R72") (pin "2") (pinfunction "2_2") (pintype "passive"))
      (node (ref "U13") (pin "1") (pinfunction "A_1") (pintype "passive"))
    )
    (net (code "90") (name "Net-(U14-A)") (class "Default")
      (node (ref "R73") (pin "2") (pinfunction "2_2") (pintype "passive"))
      (node (ref "U14") (pin "1") (pinfunction "A_1") (pintype "passive"))
    )
    (net (code "91") (name "Net-(U15-A)") (class "Default")
      (node (ref "R74") (pin "2") (pinfunction "2_2") (pintype "passive"))
      (node (ref "U15") (pin "1") (pinfunction "A_1") (pintype "passive"))
    )
    (net (code "92") (name "Net-(U16-A)") (class "Default")
      (node (ref "R83") (pin "2") (pinfunction "2_2") (pintype "passive"))
      (node (ref "U16") (pin "1") (pinfunction "A_1") (pintype "passive"))
    )
    (net (code "93") (name "Net-(U17-A)") (class "Default")
      (node (ref "R84") (pin "2") (pinfunction "2_2") (pintype "passive"))
      (node (ref "U17") (pin "1") (pinfunction "A_1") (pintype "passive"))
    )
    (net (code "94") (name "Net-(U18-A)") (class "Default")
      (node (ref "R85") (pin "2") (pinfunction "2_2") (pintype "passive"))
      (node (ref "U18") (pin "1") (pinfunction "A_1") (pintype "passive"))
    )
    (net (code "95") (name "Net-(U19-A)") (class "Default")
      (node (ref "R86") (pin "2") (pinfunction "2_2") (pintype "passive"))
      (node (ref "U19") (pin "1") (pinfunction "A_1") (pintype "passive"))
    )
    (net (code "96") (name "Net-(U20-A)") (class "Default")
      (node (ref "R95") (pin "2") (pinfunction "2_2") (pintype "passive"))
      (node (ref "U20") (pin "1") (pinfunction "A_1") (pintype "passive"))
    )
    (net (code "97") (name "Net-(U21-A)") (class "Default")
      (node (ref "R96") (pin "2") (pinfunction "2_2") (pintype "passive"))
      (node (ref "U21") (pin "1") (pinfunction "A_1") (pintype "passive"))
    )
    (net (code "98") (name "Net-(U22-A)") (class "Default")
      (node (ref "R97") (pin "2") (pinfunction "2_2") (pintype "passive"))
      (node (ref "U22") (pin "1") (pinfunction "A_1") (pintype "passive"))
    )
    (net (code "99") (name "Net-(U23-A)") (class "Default")
      (node (ref "R98") (pin "2") (pinfunction "2_2") (pintype "passive"))
      (node (ref "U23") (pin "1") (pinfunction "A_1") (pintype "passive"))
    )
    (net (code "100") (name "VCC") (class "Default")
      (node (ref "R59") (pin "1") (pinfunction "1_1") (pintype "passive"))
      (node (ref "R60") (pin "1") (pinfunction "1_1") (pintype "passive"))
      (node (ref "R61") (pin "1") (pinfunction "1_1") (pintype "passive"))
      (node (ref "R62") (pin "1") (pinfunction "1_1") (pintype "passive"))
      (node (ref "R71") (pin "1") (pinfunction "1_1") (pintype "passive"))
      (node (ref "R72") (pin "1") (pinfunction "1_1") (pintype "passive"))
      (node (ref "R73") (pin "1") (pinfunction "1_1") (pintype "passive"))
      (node (ref "R74") (pin "1") (pinfunction "1_1") (pintype "passive"))
      (node (ref "R83") (pin "1") (pinfunction "1_1") (pintype "passive"))
      (node (ref "R84") (pin "1") (pinfunction "1_1") (pintype "passive"))
      (node (ref "R85") (pin "1") (pinfunction "1_1") (pintype "passive"))
      (node (ref "R86") (pin "1") (pinfunction "1_1") (pintype "passive"))
      (node (ref "R95") (pin "1") (pinfunction "1_1") (pintype "passive"))
      (node (ref "R96") (pin "1") (pinfunction "1_1") (pintype "passive"))
      (node (ref "R97") (pin "1") (pinfunction "1_1") (pintype "passive"))
      (node (ref "R98") (pin "1") (pinfunction "1_1") (pintype "passive"))
    )
  )
)
